# Brians_test_board_1.net
KiCad netlist of a schematic drawn in EAGLE
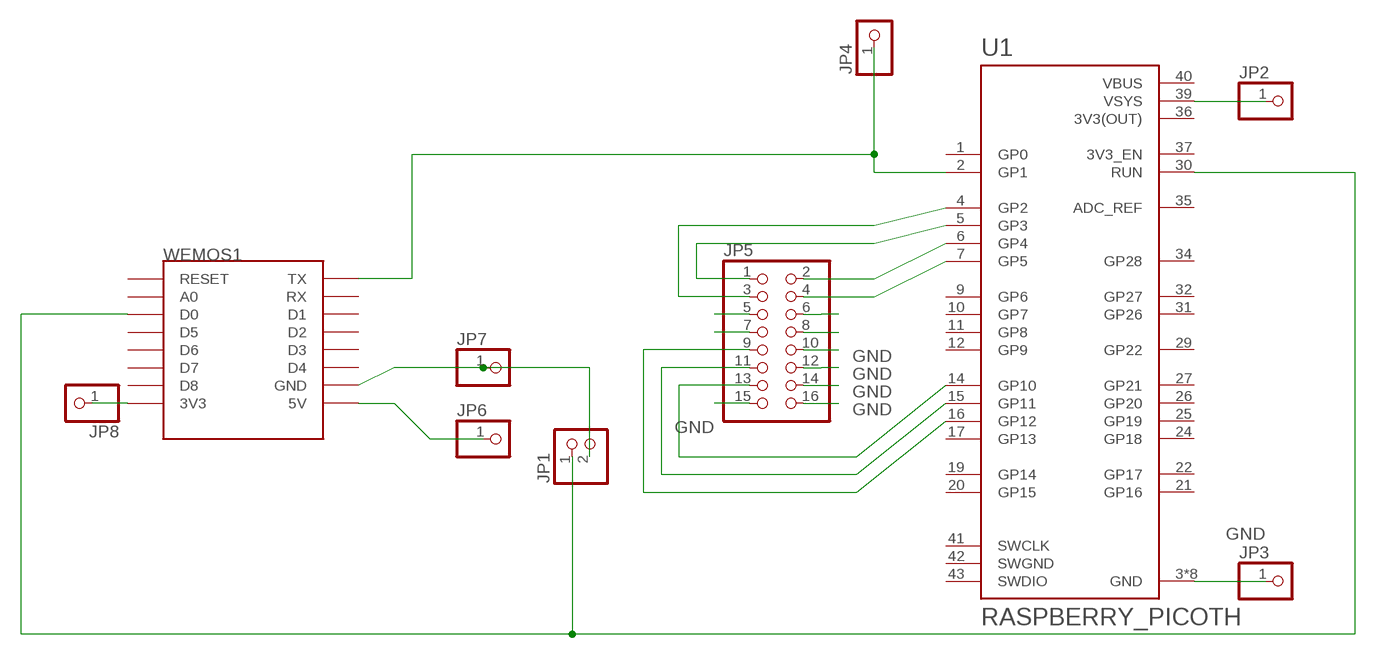
[diagram p0: schematic, sheet 1]

(export (version "E")
  (design (tool "Eeschema 10.0.6"))
  (components
    (comp (ref "JP1")
      (value "PINHD-1X2")
      (footprint "eagle-import:1X02")
      (libsource (lib "eagle-import") (part "PINHD-1X2"))
    )
    (comp (ref "JP2")
      (value "PINHD-1X1")
      (footprint "eagle-import:1X01")
      (libsource (lib "eagle-import") (part "PINHD-1X1"))
    )
    (comp (ref "JP3")
      (value "PINHD-1X1")
      (footprint "eagle-import:1X01")
      (libsource (lib "eagle-import") (part "PINHD-1X1"))
    )
    (comp (ref "JP4")
      (value "PINHD-1X1")
      (footprint "eagle-import:1X01")
      (libsource (lib "eagle-import") (part "PINHD-1X1"))
    )
    (comp (ref "JP5")
      (value "PINHD-2X8")
      (footprint "eagle-import:2X08")
      (libsource (lib "eagle-import") (part "PINHD-2X8"))
    )
    (comp (ref "JP6")
      (value "PINHD-1X1")
      (footprint "eagle-import:1X01")
      (libsource (lib "eagle-import") (part "PINHD-1X1"))
    )
    (comp (ref "JP7")
      (value "PINHD-1X1")
      (footprint "eagle-import:1X01")
      (libsource (lib "eagle-import") (part "PINHD-1X1"))
    )
    (comp (ref "JP8")
      (value "PINHD-1X1")
      (footprint "eagle-import:1X01")
      (libsource (lib "eagle-import") (part "PINHD-1X1"))
    )
    (comp (ref "U1")
      (value "RASPBERRY_PICOTH")
      (footprint "eagle-import:PICO-PKG-TH")
      (libsource (lib "eagle-import") (part "RASPBERRY_PICOTH"))
    )
    (comp (ref "WEMOS1")
      (value "WEMOS-D1-MINI")
      (footprint "eagle-import:WEMOS-D1-MINI")
      (libsource (lib "eagle-import") (part "WEMOS-D1-MINI"))
    )
  )
  (nets
    (net (code "1") (name "/3V3(OUT)") (class "Default")
      (node (ref "U1") (pin "36") (pinfunction "3V3(OUT)_36") (pintype "power_in"))
    )
    (net (code "2") (name "/GND") (class "Default")
      (node (ref "JP3") (pin "1") (pinfunction "1_1") (pintype "passive"))
      (node (ref "JP5") (pin "10") (pinfunction "10_10") (pintype "passive"))
      (node (ref "JP5") (pin "12") (pinfunction "12_12") (pintype "passive"))
      (node (ref "JP5") (pin "14") (pinfunction "14_14") (pintype "passive"))
      (node (ref "JP5") (pin "15") (pinfunction "15_15") (pintype "passive"))
      (node (ref "JP5") (pin "16") (pinfunction "16_16") (pintype "passive"))
      (node (ref "U1") (pin "13") (pinfunction "GND_13") (pintype "power_in"))
      (node (ref "U1") (pin "18") (pinfunction "GND_18") (pintype "power_in"))
      (node (ref "U1") (pin "23") (pinfunction "GND_23") (pintype "power_in"))
      (node (ref "U1") (pin "28") (pinfunction "GND_28") (pintype "power_in"))
      (node (ref "U1") (pin "3") (pinfunction "GND_3") (pintype "power_in"))
      (node (ref "U1") (pin "33") (pinfunction "GND_33") (pintype "power_in"))
      (node (ref "U1") (pin "38") (pinfunction "GND_38") (pintype "power_in"))
      (node (ref "U1") (pin "8") (pinfunction "GND_8") (pintype "power_in"))
    )
    (net (code "3") (name "/SWGND") (class "Default")
      (node (ref "U1") (pin "42") (pinfunction "SWGND_42") (pintype "power_in"))
    )
    (net (code "4") (name "/VBUS") (class "Default")
      (node (ref "U1") (pin "40") (pinfunction "VBUS_40") (pintype "power_in"))
    )
    (net (code "5") (name "Net-(JP1-Pad2)") (class "Default")
      (node (ref "JP1") (pin "2") (pinfunction "2_2") (pintype "passive"))
      (node (ref "JP7") (pin "1") (pinfunction "1_1") (pintype "passive"))
      (node (ref "WEMOS1") (pin "GND") (pinfunction "GND_GND") (pintype "bidirectional"))
    )
    (net (code "6") (name "Net-(JP6-Pad1)") (class "Default")
      (node (ref "JP6") (pin "1") (pinfunction "1_1") (pintype "passive"))
      (node (ref "WEMOS1") (pin "5V") (pinfunction "5V_5V") (pintype "bidirectional"))
    )
    (net (code "7") (name "Net-(JP8-Pad1)") (class "Default")
      (node (ref "JP8") (pin "1") (pinfunction "1_1") (pintype "passive"))
      (node (ref "WEMOS1") (pin "3V3") (pinfunction "3V3_3V3") (pintype "bidirectional"))
    )
    (net (code "8") (name "Net-(U1-GP1)") (class "Default")
      (node (ref "JP4") (pin "1") (pinfunction "1_1") (pintype "passive"))
      (node (ref "U1") (pin "2") (pinfunction "GP1_2") (pintype "bidirectional"))
      (node (ref "WEMOS1") (pin "TX") (pinfunction "TX_TX") (pintype "bidirectional"))
    )
    (net (code "9") (name "Net-(U1-GP2)") (class "Default")
      (node (ref "JP5") (pin "3") (pinfunction "3_3") (pintype "passive"))
      (node (ref "U1") (pin "4") (pinfunction "GP2_4") (pintype "bidirectional"))
    )
    (net (code "10") (name "Net-(U1-GP3)") (class "Default")
      (node (ref "JP5") (pin "1") (pinfunction "1_1") (pintype "passive"))
      (node (ref "U1") (pin "5") (pinfunction "GP3_5") (pintype "bidirectional"))
    )
    (net (code "11") (name "Net-(U1-GP4)") (class "Default")
      (node (ref "JP5") (pin "2") (pinfunction "2_2") (pintype "passive"))
      (node (ref "U1") (pin "6") (pinfunction "GP4_6") (pintype "bidirectional"))
    )
    (net (code "12") (name "Net-(U1-GP5)") (class "Default")
      (node (ref "JP5") (pin "4") (pinfunction "4_4") (pintype "passive"))
      (node (ref "U1") (pin "7") (pinfunction "GP5_7") (pintype "bidirectional"))
    )
    (net (code "13") (name "Net-(U1-GP10)") (class "Default")
      (node (ref "JP5") (pin "13") (pinfunction "13_13") (pintype "passive"))
      (node (ref "U1") (pin "14") (pinfunction "GP10_14") (pintype "bidirectional"))
    )
    (net (code "14") (name "Net-(U1-GP11)") (class "Default")
      (node (ref "JP5") (pin "11") (pinfunction "11_11") (pintype "passive"))
      (node (ref "U1") (pin "15") (pinfunction "GP11_15") (pintype "bidirectional"))
    )
    (net (code "15") (name "Net-(U1-GP12)") (class "Default")
      (node (ref "JP5") (pin "9") (pinfunction "9_9") (pintype "passive"))
      (node (ref "U1") (pin "16") (pinfunction "GP12_16") (pintype "bidirectional"))
    )
    (net (code "16") (name "Net-(U1-RUN)") (class "Default")
      (node (ref "JP1") (pin "1") (pinfunction "1_1") (pintype "passive"))
      (node (ref "U1") (pin "30") (pinfunction "RUN_30") (pintype "input"))
      (node (ref "WEMOS1") (pin "D0") (pinfunction "D0_D0") (pintype "bidirectional"))
    )
    (net (code "17") (name "Net-(U1-VSYS)") (class "Default")
      (node (ref "JP2") (pin "1") (pinfunction "1_1") (pintype "passive"))
      (node (ref "U1") (pin "39") (pinfunction "VSYS_39") (pintype "power_in"))
    )
    (net (code "18") (name "unconnected-(JP5-Pad5)") (class "Default")
      (node (ref "JP5") (pin "5") (pinfunction "5_5") (pintype "passive"))
    )
    (net (code "19") (name "unconnected-(JP5-Pad6)") (class "Default")
      (node (ref "JP5") (pin "6") (pinfunction "6_6") (pintype "passive"))
    )
    (net (code "20") (name "unconnected-(JP5-Pad7)") (class "Default")
      (node (ref "JP5") (pin "7") (pinfunction "7_7") (pintype "passive"))
    )
    (net (code "21") (name "unconnected-(JP5-Pad8)") (class "Default")
      (node (ref "JP5") (pin "8") (pinfunction "8_8") (pintype "passive"))
    )
    (net (code "22") (name "unconnected-(U1-3V3_EN-Pad37)") (class "Default")
      (node (ref "U1") (pin "37") (pinfunction "3V3_EN_37") (pintype "input"))
    )
    (net (code "23") (name "unconnected-(U1-ADC_REF-Pad35)") (class "Default")
      (node (ref "U1") (pin "35") (pinfunction "ADC_REF_35") (pintype "input"))
    )
    (net (code "24") (name "unconnected-(U1-GP0-Pad1)") (class "Default")
      (node (ref "U1") (pin "1") (pinfunction "GP0_1") (pintype "bidirectional"))
    )
    (net (code "25") (name "unconnected-(U1-GP6-Pad9)") (class "Default")
      (node (ref "U1") (pin "9") (pinfunction "GP6_9") (pintype "bidirectional"))
    )
    (net (code "26") (name "unconnected-(U1-GP7-Pad10)") (class "Default")
      (node (ref "U1") (pin "10") (pinfunction "GP7_10") (pintype "bidirectional"))
    )
    (net (code "27") (name "unconnected-(U1-GP8-Pad11)") (class "Default")
      (node (ref "U1") (pin "11") (pinfunction "GP8_11") (pintype "bidirectional"))
    )
    (net (code "28") (name "unconnected-(U1-GP9-Pad12)") (class "Default")
      (node (ref "U1") (pin "12") (pinfunction "GP9_12") (pintype "bidirectional"))
    )
    (net (code "29") (name "unconnected-(U1-GP13-Pad17)") (class "Default")
      (node (ref "U1") (pin "17") (pinfunction "GP13_17") (pintype "bidirectional"))
    )
    (net (code "30") (name "unconnected-(U1-GP14-Pad19)") (class "Default")
      (node (ref "U1") (pin "19") (pinfunction "GP14_19") (pintype "bidirectional"))
    )
    (net (code "31") (name "unconnected-(U1-GP15-Pad20)") (class "Default")
      (node (ref "U1") (pin "20") (pinfunction "GP15_20") (pintype "bidirectional"))
    )
    (net (code "32") (name "unconnected-(U1-GP16-Pad21)") (class "Default")
      (node (ref "U1") (pin "21") (pinfunction "GP16_21") (pintype "bidirectional"))
    )
    (net (code "33") (name "unconnected-(U1-GP17-Pad22)") (class "Default")
      (node (ref "U1") (pin "22") (pinfunction "GP17_22") (pintype "bidirectional"))
    )
    (net (code "34") (name "unconnected-(U1-GP18-Pad24)") (class "Default")
      (node (ref "U1") (pin "24") (pinfunction "GP18_24") (pintype "bidirectional"))
    )
    (net (code "35") (name "unconnected-(U1-GP19-Pad25)") (class "Default")
      (node (ref "U1") (pin "25") (pinfunction "GP19_25") (pintype "bidirectional"))
    )
    (net (code "36") (name "unconnected-(U1-GP20-Pad26)") (class "Default")
      (node (ref "U1") (pin "26") (pinfunction "GP20_26") (pintype "bidirectional"))
    )
    (net (code "37") (name "unconnected-(U1-GP21-Pad27)") (class "Default")
      (node (ref "U1") (pin "27") (pinfunction "GP21_27") (pintype "bidirectional"))
    )
    (net (code "38") (name "unconnected-(U1-GP22-Pad29)") (class "Default")
      (node (ref "U1") (pin "29") (pinfunction "GP22_29") (pintype "bidirectional"))
    )
    (net (code "39") (name "unconnected-(U1-GP26-Pad31)") (class "Default")
      (node (ref "U1") (pin "31") (pinfunction "GP26_31") (pintype "bidirectional"))
    )
    (net (code "40") (name "unconnected-(U1-GP27-Pad32)") (class "Default")
      (node (ref "U1") (pin "32") (pinfunction "GP27_32") (pintype "bidirectional"))
    )
    (net (code "41") (name "unconnected-(U1-GP28-Pad34)") (class "Default")
      (node (ref "U1") (pin "34") (pinfunction "GP28_34") (pintype "bidirectional"))
    )
    (net (code "42") (name "unconnected-(U1-SWCLK-Pad41)") (class "Default")
      (node (ref "U1") (pin "41") (pinfunction "SWCLK_41") (pintype "input"))
    )
    (net (code "43") (name "unconnected-(U1-SWDIO-Pad43)") (class "Default")
      (node (ref "U1") (pin "43") (pinfunction "SWDIO_43") (pintype "bidirectional"))
    )
    (net (code "44") (name "unconnected-(WEMOS1-PadA0)") (class "Default")
      (node (ref "WEMOS1") (pin "A0") (pinfunction "A0_A0") (pintype "bidirectional"))
    )
    (net (code "45") (name "unconnected-(WEMOS1-PadD1)") (class "Default")
      (node (ref "WEMOS1") (pin "D1") (pinfunction "D1_D1") (pintype "bidirectional"))
    )
    (net (code "46") (name "unconnected-(WEMOS1-PadD2)") (class "Default")
      (node (ref "WEMOS1") (pin "D2") (pinfunction "D2_D2") (pintype "bidirectional"))
    )
    (net (code "47") (name "unconnected-(WEMOS1-PadD3)") (class "Default")
      (node (ref "WEMOS1") (pin "D3") (pinfunction "D3_D3") (pintype "bidirectional"))
    )
    (net (code "48") (name "unconnected-(WEMOS1-PadD4)") (class "Default")
      (node (ref "WEMOS1") (pin "D4") (pinfunction "D4_D4") (pintype "bidirectional"))
    )
    (net (code "49") (name "unconnected-(WEMOS1-PadD5)") (class "Default")
      (node (ref "WEMOS1") (pin "D5") (pinfunction "D5_D5") (pintype "bidirectional"))
    )
    (net (code "50") (name "unconnected-(WEMOS1-PadD6)") (class "Default")
      (node (ref "WEMOS1") (pin "D6") (pinfunction "D6_D6") (pintype "bidirectional"))
    )
    (net (code "51") (name "unconnected-(WEMOS1-PadD7)") (class "Default")
      (node (ref "WEMOS1") (pin "D7") (pinfunction "D7_D7") (pintype "bidirectional"))
    )
    (net (code "52") (name "unconnected-(WEMOS1-PadD8)") (class "Default")
      (node (ref "WEMOS1") (pin "D8") (pinfunction "D8_D8") (pintype "bidirectional"))
    )
    (net (code "53") (name "unconnected-(WEMOS1-PadRESET)") (class "Default")
      (node (ref "WEMOS1") (pin "RESET") (pinfunction "RESET_RESET") (pintype "bidirectional"))
    )
    (net (code "54") (name "unconnected-(WEMOS1-PadRX)") (class "Default")
      (node (ref "WEMOS1") (pin "RX") (pinfunction "RX_RX") (pintype "bidirectional"))
    )
  )
)
